# ac-adapter.net
KiCad netlist of a schematic drawn in EAGLE
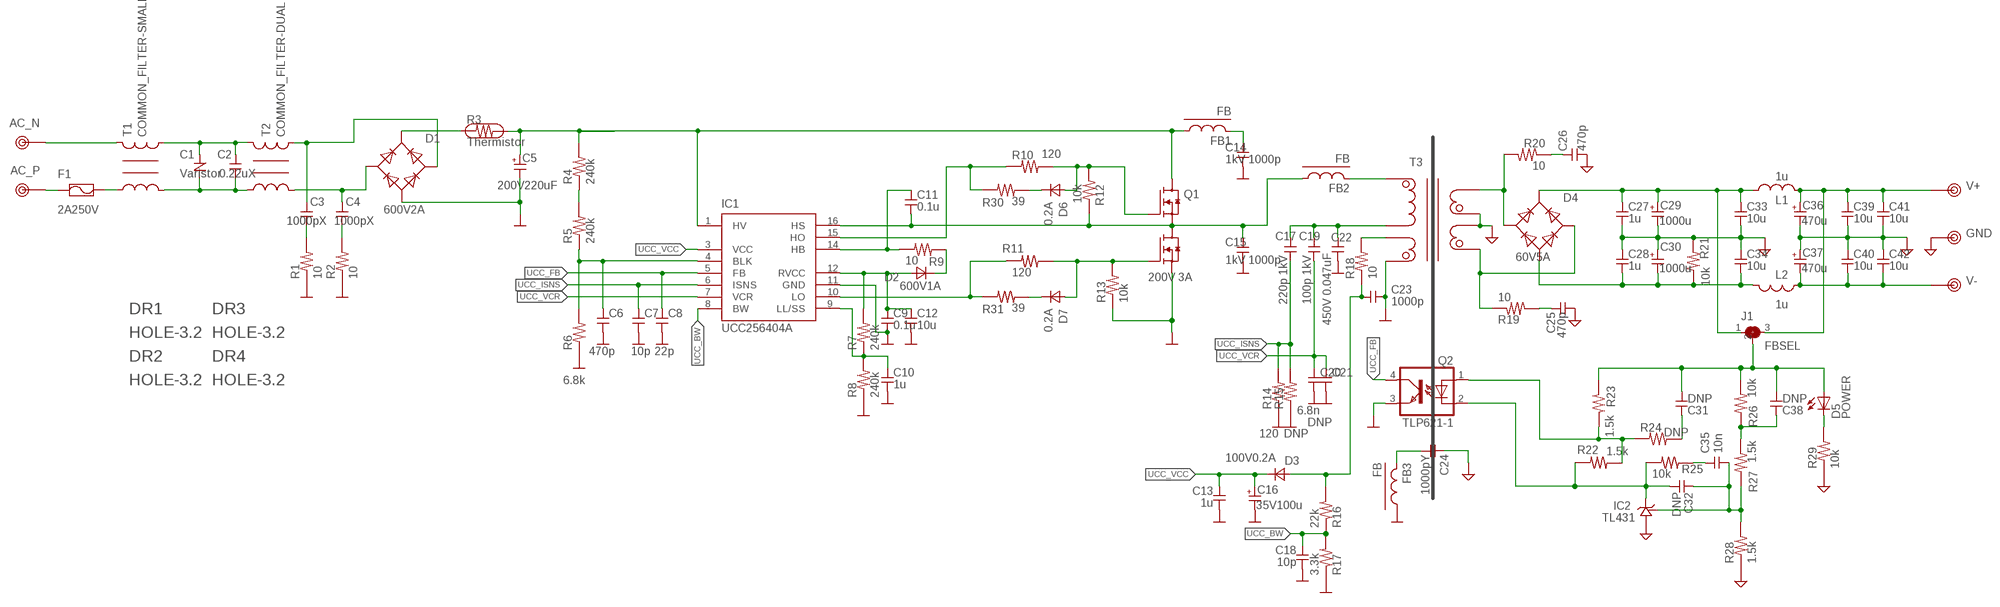
[diagram p0: schematic, sheet 1]

(export (version "E")
  (design (tool "Eeschema 10.0.6"))
  (components
    (comp (ref "C1")
      (value "Varistor")
      (footprint "eagle-import:V050")
      (libsource (lib "eagle-import") (part "VARISTOR"))
    )
    (comp (ref "C2")
      (value "0.22uX")
      (footprint "eagle-import:X-CAPACITER")
      (libsource (lib "eagle-import") (part "C-X"))
    )
    (comp (ref "C3")
      (value "1000pX")
      (footprint "eagle-import:3216")
      (libsource (lib "eagle-import") (part "C-3216"))
    )
    (comp (ref "C4")
      (value "1000pX")
      (footprint "eagle-import:3216")
      (libsource (lib "eagle-import") (part "C-3216"))
    )
    (comp (ref "C5")
      (value "200V220uF")
      (footprint "eagle-import:E5-16A3")
      (libsource (lib "eagle-import") (part "CPOLE7.5-16A3"))
    )
    (comp (ref "C6")
      (value "470p")
      (footprint "eagle-import:1608")
      (libsource (lib "eagle-import") (part "C-1608"))
    )
    (comp (ref "C7")
      (value "10p")
      (footprint "eagle-import:1608")
      (libsource (lib "eagle-import") (part "C-1608"))
    )
    (comp (ref "C8")
      (value "22p")
      (footprint "eagle-import:1608")
      (libsource (lib "eagle-import") (part "C-1608"))
    )
    (comp (ref "C9")
      (value "0.1u")
      (footprint "eagle-import:1608")
      (libsource (lib "eagle-import") (part "C-1608"))
    )
    (comp (ref "C10")
      (value "1u")
      (footprint "eagle-import:1608")
      (libsource (lib "eagle-import") (part "C-1608"))
    )
    (comp (ref "C11")
      (value "0.1u")
      (footprint "eagle-import:1608")
      (libsource (lib "eagle-import") (part "C-1608"))
    )
    (comp (ref "C12")
      (value "10u")
      (footprint "eagle-import:2012")
      (libsource (lib "eagle-import") (part "C-2012"))
    )
    (comp (ref "C13")
      (value "1u")
      (footprint "eagle-import:1608")
      (libsource (lib "eagle-import") (part "C-1608"))
    )
    (comp (ref "C14")
      (value "1kV 1000p")
      (footprint "eagle-import:3225")
      (libsource (lib "eagle-import") (part "C-3225"))
    )
    (comp (ref "C15")
      (value "1kV 1000p")
      (footprint "eagle-import:3225")
      (libsource (lib "eagle-import") (part "C-3225"))
    )
    (comp (ref "C16")
      (value "35V100u")
      (footprint "eagle-import:E2,5-8")
      (libsource (lib "eagle-import") (part "CPOLE2.5-8"))
    )
    (comp (ref "C17")
      (value "220p 1kV")
      (footprint "eagle-import:3225")
      (libsource (lib "eagle-import") (part "C-3225"))
    )
    (comp (ref "C18")
      (value "10p")
      (footprint "eagle-import:1608")
      (libsource (lib "eagle-import") (part "C-1608"))
    )
    (comp (ref "C19")
      (value "100p 1kV")
      (footprint "eagle-import:3225")
      (libsource (lib "eagle-import") (part "C-3225"))
    )
    (comp (ref "C20")
      (value "6.8n")
      (footprint "eagle-import:1608")
      (libsource (lib "eagle-import") (part "C-1608"))
    )
    (comp (ref "C21")
      (value "DNP")
      (footprint "eagle-import:1608")
      (libsource (lib "eagle-import") (part "C-1608"))
    )
    (comp (ref "C22")
      (value "450V 0.047uF")
      (footprint "eagle-import:C125")
      (libsource (lib "eagle-import") (part "C-12.5"))
    )
    (comp (ref "C23")
      (value "1000p")
      (footprint "eagle-import:1608")
      (libsource (lib "eagle-import") (part "C-1608"))
    )
    (comp (ref "C24")
      (value "1000pY")
      (footprint "eagle-import:Y-CAPACITER")
      (libsource (lib "eagle-import") (part "C-Y"))
    )
    (comp (ref "C25")
      (value "470p")
      (footprint "eagle-import:1608")
      (libsource (lib "eagle-import") (part "C-1608"))
    )
    (comp (ref "C26")
      (value "470p")
      (footprint "eagle-import:1608")
      (libsource (lib "eagle-import") (part "C-1608"))
    )
    (comp (ref "C27")
      (value "1u")
      (footprint "eagle-import:2012-2")
      (libsource (lib "eagle-import") (part "C-2012-2"))
    )
    (comp (ref "C28")
      (value "1u")
      (footprint "eagle-import:2012-2")
      (libsource (lib "eagle-import") (part "C-2012-2"))
    )
    (comp (ref "C29")
      (value "1000u")
      (footprint "eagle-import:E5-13")
      (libsource (lib "eagle-import") (part "CPOLE5-13"))
    )
    (comp (ref "C30")
      (value "1000u")
      (footprint "eagle-import:E5-13")
      (libsource (lib "eagle-import") (part "CPOLE5-13"))
    )
    (comp (ref "C31")
      (value "DNP")
      (footprint "eagle-import:1608")
      (libsource (lib "eagle-import") (part "C-1608"))
    )
    (comp (ref "C32")
      (value "DNP")
      (footprint "eagle-import:1608")
      (libsource (lib "eagle-import") (part "C-1608"))
    )
    (comp (ref "C33")
      (value "10u")
      (footprint "eagle-import:3225-3")
      (libsource (lib "eagle-import") (part "C-3225-3"))
    )
    (comp (ref "C34")
      (value "10u")
      (footprint "eagle-import:3225-3")
      (libsource (lib "eagle-import") (part "C-3225-3"))
    )
    (comp (ref "C35")
      (value "10n")
      (footprint "eagle-import:1608")
      (libsource (lib "eagle-import") (part "C-1608"))
    )
    (comp (ref "C36")
      (value "470u")
      (footprint "eagle-import:E5-10")
      (libsource (lib "eagle-import") (part "CPOLE5-10"))
    )
    (comp (ref "C37")
      (value "470u")
      (footprint "eagle-import:E5-10")
      (libsource (lib "eagle-import") (part "CPOLE5-10"))
    )
    (comp (ref "C38")
      (value "DNP")
      (footprint "eagle-import:1608")
      (libsource (lib "eagle-import") (part "C-1608"))
    )
    (comp (ref "C39")
      (value "10u")
      (footprint "eagle-import:3225-3")
      (libsource (lib "eagle-import") (part "C-3225-3"))
    )
    (comp (ref "C40")
      (value "10u")
      (footprint "eagle-import:3225-3")
      (libsource (lib "eagle-import") (part "C-3225-3"))
    )
    (comp (ref "C41")
      (value "10u")
      (footprint "eagle-import:4532-2")
      (libsource (lib "eagle-import") (part "C-4532-2"))
    )
    (comp (ref "C42")
      (value "10u")
      (footprint "eagle-import:4532-2")
      (libsource (lib "eagle-import") (part "C-4532-2"))
    )
    (comp (ref "D1")
      (value "600V2A")
      (footprint "eagle-import:GBU8A")
      (libsource (lib "eagle-import") (part "DIODE4-GBU8A"))
    )
    (comp (ref "D2")
      (value "600V1A")
      (footprint "eagle-import:SOD123")
      (libsource (lib "eagle-import") (part "DIODE-1N4148W"))
    )
    (comp (ref "D3")
      (value "100V0.2A")
      (footprint "eagle-import:SOD123")
      (libsource (lib "eagle-import") (part "DIODE-1N4148W"))
    )
    (comp (ref "D4")
      (value "60V5A")
      (footprint "eagle-import:RBA-406")
      (libsource (lib "eagle-import") (part "DIODE4-RBA406B"))
    )
    (comp (ref "D5")
      (value "POWER")
      (footprint "eagle-import:D1608")
      (libsource (lib "eagle-import") (part "LED-SMD1608"))
    )
    (comp (ref "D6")
      (value "0.2A")
      (footprint "eagle-import:SOD123")
      (libsource (lib "eagle-import") (part "DIODE-1N4148W"))
    )
    (comp (ref "D7")
      (value "0.2A")
      (footprint "eagle-import:SOD123")
      (libsource (lib "eagle-import") (part "DIODE-1N4148W"))
    )
    (comp (ref "DR1")
      (value "HOLE-3.2")
      (footprint "eagle-import:HOLE_3.2")
      (libsource (lib "eagle-import") (part "HOLE-3.2"))
    )
    (comp (ref "DR2")
      (value "HOLE-3.2")
      (footprint "eagle-import:HOLE_3.2")
      (libsource (lib "eagle-import") (part "HOLE-3.2"))
    )
    (comp (ref "DR3")
      (value "HOLE-3.2")
      (footprint "eagle-import:HOLE_3.2")
      (libsource (lib "eagle-import") (part "HOLE-3.2"))
    )
    (comp (ref "DR4")
      (value "HOLE-3.2")
      (footprint "eagle-import:HOLE_3.2")
      (libsource (lib "eagle-import") (part "HOLE-3.2"))
    )
    (comp (ref "F1")
      (value "2A250V")
      (footprint "eagle-import:FUSE-5")
      (libsource (lib "eagle-import") (part "FUSE-5"))
    )
    (comp (ref "FB1")
      (value "FB")
      (footprint "eagle-import:2012-FB")
      (libsource (lib "eagle-import") (part "FB2012-FB"))
    )
    (comp (ref "FB2")
      (value "FB")
      (footprint "eagle-import:3216-J")
      (libsource (lib "eagle-import") (part "FB-3216"))
    )
    (comp (ref "FB3")
      (value "FB")
      (footprint "eagle-import:2012-FB")
      (libsource (lib "eagle-import") (part "FB2012-FB"))
    )
    (comp (ref "IC1")
      (value "UCC256404A")
      (footprint "eagle-import:SO16-LACK3-13")
      (libsource (lib "eagle-import") (part "UCC25640X"))
    )
    (comp (ref "IC2")
      (value "TL431")
      (footprint "eagle-import:TO-92")
      (libsource (lib "eagle-import") (part "TL431"))
    )
    (comp (ref "J1")
      (value "FBSEL")
      (footprint "eagle-import:2012-3-J")
      (libsource (lib "eagle-import") (part "SJ-3-2012"))
    )
    (comp (ref "L1")
      (value "1u")
      (footprint "eagle-import:L5-7,5")
      (libsource (lib "eagle-import") (part "L-5"))
    )
    (comp (ref "L2")
      (value "1u")
      (footprint "eagle-import:L5-7,5")
      (libsource (lib "eagle-import") (part "L-5"))
    )
    (comp (ref "Q1")
      (value "200V 3A")
      (footprint "eagle-import:NMOS-FET_HALF")
      (libsource (lib "eagle-import") (part "NMOS_FET_HALF"))
    )
    (comp (ref "Q2")
      (value "TLP621-1")
      (footprint "eagle-import:DIL04")
      (libsource (lib "eagle-import") (part "TLP621-1"))
    )
    (comp (ref "R1")
      (value "10")
      (footprint "eagle-import:2012")
      (libsource (lib "eagle-import") (part "R-2012"))
    )
    (comp (ref "R2")
      (value "10")
      (footprint "eagle-import:2012")
      (libsource (lib "eagle-import") (part "R-2012"))
    )
    (comp (ref "R3")
      (value "Thermistor")
      (footprint "eagle-import:THERMISTOR090")
      (libsource (lib "eagle-import") (part "THERMISTOR"))
    )
    (comp (ref "R4")
      (value "240k")
      (footprint "eagle-import:1608")
      (libsource (lib "eagle-import") (part "R-1608"))
    )
    (comp (ref "R5")
      (value "240k")
      (footprint "eagle-import:1608")
      (libsource (lib "eagle-import") (part "R-1608"))
    )
    (comp (ref "R6")
      (value "6.8k")
      (footprint "eagle-import:1608")
      (libsource (lib "eagle-import") (part "R-1608"))
    )
    (comp (ref "R7")
      (value "240k")
      (footprint "eagle-import:1608")
      (libsource (lib "eagle-import") (part "R-1608"))
    )
    (comp (ref "R8")
      (value "240k")
      (footprint "eagle-import:1608")
      (libsource (lib "eagle-import") (part "R-1608"))
    )
    (comp (ref "R9")
      (value "10")
      (footprint "eagle-import:1608")
      (libsource (lib "eagle-import") (part "R-1608"))
    )
    (comp (ref "R10")
      (value "120")
      (footprint "eagle-import:1608")
      (libsource (lib "eagle-import") (part "R-1608"))
    )
    (comp (ref "R11")
      (value "120")
      (footprint "eagle-import:1608")
      (libsource (lib "eagle-import") (part "R-1608"))
    )
    (comp (ref "R12")
      (value "10k")
      (footprint "eagle-import:1608")
      (libsource (lib "eagle-import") (part "R-1608"))
    )
    (comp (ref "R13")
      (value "10k")
      (footprint "eagle-import:1608")
      (libsource (lib "eagle-import") (part "R-1608"))
    )
    (comp (ref "R14")
      (value "120")
      (footprint "eagle-import:1608")
      (libsource (lib "eagle-import") (part "R-1608"))
    )
    (comp (ref "R15")
      (value "DNP")
      (footprint "eagle-import:1608")
      (libsource (lib "eagle-import") (part "R-1608"))
    )
    (comp (ref "R16")
      (value "22k")
      (footprint "eagle-import:1608")
      (libsource (lib "eagle-import") (part "R-1608"))
    )
    (comp (ref "R17")
      (value "3.3k")
      (footprint "eagle-import:1608")
      (libsource (lib "eagle-import") (part "R-1608"))
    )
    (comp (ref "R18")
      (value "10")
      (footprint "eagle-import:2012")
      (libsource (lib "eagle-import") (part "R-2012"))
    )
    (comp (ref "R19")
      (value "10")
      (footprint "eagle-import:2012")
      (libsource (lib "eagle-import") (part "R-2012"))
    )
    (comp (ref "R20")
      (value "10")
      (footprint "eagle-import:2012")
      (libsource (lib "eagle-import") (part "R-2012"))
    )
    (comp (ref "R21")
      (value "10k")
      (footprint "eagle-import:1608")
      (libsource (lib "eagle-import") (part "R-1608"))
    )
    (comp (ref "R22")
      (value "1.5k")
      (footprint "eagle-import:1608")
      (libsource (lib "eagle-import") (part "R-1608"))
    )
    (comp (ref "R23")
      (value "1.5k")
      (footprint "eagle-import:1608")
      (libsource (lib "eagle-import") (part "R-1608"))
    )
    (comp (ref "R24")
      (value "DNP")
      (footprint "eagle-import:1608")
      (libsource (lib "eagle-import") (part "R-1608"))
    )
    (comp (ref "R25")
      (value "10k")
      (footprint "eagle-import:1608")
      (libsource (lib "eagle-import") (part "R-1608"))
    )
    (comp (ref "R26")
      (value "10k")
      (footprint "eagle-import:1608")
      (libsource (lib "eagle-import") (part "R-1608"))
    )
    (comp (ref "R27")
      (value "1.5k")
      (footprint "eagle-import:1608")
      (libsource (lib "eagle-import") (part "R-1608"))
    )
    (comp (ref "R28")
      (value "1.5k")
      (footprint "eagle-import:1608")
      (libsource (lib "eagle-import") (part "R-1608"))
    )
    (comp (ref "R29")
      (value "10k")
      (footprint "eagle-import:1608")
      (libsource (lib "eagle-import") (part "R-1608"))
    )
    (comp (ref "R30")
      (value "39")
      (footprint "eagle-import:1608")
      (libsource (lib "eagle-import") (part "R-1608"))
    )
    (comp (ref "R31")
      (value "39")
      (footprint "eagle-import:1608")
      (libsource (lib "eagle-import") (part "R-1608"))
    )
    (comp (ref "T1")
      (value "COMMON_FILTER-SMALL")
      (footprint "eagle-import:COMMON_FILTER__SMALL")
      (libsource (lib "eagle-import") (part "COMMON_FILTER-SMALL"))
    )
    (comp (ref "T2")
      (value "COMMON_FILTER-DUAL")
      (footprint "eagle-import:SU10VFC-DUAL")
      (libsource (lib "eagle-import") (part "COMMON_FILTER-DUAL"))
    )
    (comp (ref "T3")
      (value "TRANSFORMAER_FLYBACK-ETD34")
      (footprint "eagle-import:BETD34LLC")
      (libsource (lib "eagle-import") (part "TRANSFORMAER_FLYBACK-ETD34"))
    )
    (comp (ref "TP1")
      (value "AC_N")
      (footprint "eagle-import:TESTPIN-LARGE")
      (libsource (lib "eagle-import") (part "TESTPIN-LARGE"))
    )
    (comp (ref "TP2")
      (value "AC_P")
      (footprint "eagle-import:TESTPIN-LARGE")
      (libsource (lib "eagle-import") (part "TESTPIN-LARGE"))
    )
    (comp (ref "TP3")
      (value "V+")
      (footprint "eagle-import:TESTPIN-LARGE")
      (libsource (lib "eagle-import") (part "TESTPIN-LARGE"))
    )
    (comp (ref "TP4")
      (value "V-")
      (footprint "eagle-import:TESTPIN-LARGE")
      (libsource (lib "eagle-import") (part "TESTPIN-LARGE"))
    )
    (comp (ref "TP5")
      (value "GND")
      (footprint "eagle-import:TESTPIN-LARGE")
      (libsource (lib "eagle-import") (part "TESTPIN-LARGE"))
    )
  )
  (nets
    (net (code "1") (name "GND") (class "Default")
      (node (ref "C24") (pin "1") (pinfunction "1_1") (pintype "passive"))
      (node (ref "C25") (pin "2") (pinfunction "2_2") (pintype "passive"))
      (node (ref "C26") (pin "2") (pinfunction "2_2") (pintype "passive"))
      (node (ref "C27") (pin "2") (pinfunction "2_2") (pintype "passive"))
      (node (ref "C28") (pin "1") (pinfunction "1_1") (pintype "passive"))
      (node (ref "C29") (pin "-") (pinfunction "2_-") (pintype "passive"))
      (node (ref "C30") (pin "+") (pinfunction "1_+") (pintype "passive"))
      (node (ref "C33") (pin "2") (pinfunction "2_2") (pintype "passive"))
      (node (ref "C34") (pin "1") (pinfunction "1_1") (pintype "passive"))
      (node (ref "C36") (pin "-") (pinfunction "2_-") (pintype "passive"))
      (node (ref "C37") (pin "+") (pinfunction "1_+") (pintype "passive"))
      (node (ref "C39") (pin "2") (pinfunction "2_2") (pintype "passive"))
      (node (ref "C40") (pin "1") (pinfunction "1_1") (pintype "passive"))
      (node (ref "C41") (pin "2") (pinfunction "2_2") (pintype "passive"))
      (node (ref "C42") (pin "1") (pinfunction "1_1") (pintype "passive"))
      (node (ref "IC2") (pin "2") (pinfunction "GND_2") (pintype "bidirectional"))
      (node (ref "R21") (pin "1") (pinfunction "1_1") (pintype "passive"))
      (node (ref "R28") (pin "1") (pinfunction "1_1") (pintype "passive"))
      (node (ref "R29") (pin "1") (pinfunction "1_1") (pintype "passive"))
      (node (ref "T3") (pin "11") (pinfunction "L4_N_11") (pintype "passive"))
      (node (ref "T3") (pin "8") (pinfunction "L3_P_8") (pintype "passive"))
      (node (ref "TP5") (pin "1") (pinfunction "1_1") (pintype "passive"))
    )
    (net (code "2") (name "Net-(C1-Pad1)") (class "Default")
      (node (ref "C1") (pin "1") (pinfunction "1_1") (pintype "passive"))
      (node (ref "C2") (pin "1") (pinfunction "1_1") (pintype "passive"))
      (node (ref "T1") (pin "3") (pinfunction "3_3") (pintype "passive"))
      (node (ref "T2") (pin "1") (pinfunction "1_1") (pintype "passive"))
      (node (ref "T2") (pin "5") (pinfunction "1_5") (pintype "passive"))
    )
    (net (code "3") (name "Net-(C1-Pad2)") (class "Default")
      (node (ref "C1") (pin "2") (pinfunction "2_2") (pintype "passive"))
      (node (ref "C2") (pin "2") (pinfunction "2_2") (pintype "passive"))
      (node (ref "T1") (pin "2") (pinfunction "2_2") (pintype "passive"))
      (node (ref "T2") (pin "4") (pinfunction "4_4") (pintype "passive"))
    )
    (net (code "4") (name "Net-(C3-Pad2)") (class "Default")
      (node (ref "C3") (pin "2") (pinfunction "2_2") (pintype "passive"))
      (node (ref "R1") (pin "2") (pinfunction "2_2") (pintype "passive"))
    )
    (net (code "5") (name "Net-(C4-Pad2)") (class "Default")
      (node (ref "C4") (pin "2") (pinfunction "2_2") (pintype "passive"))
      (node (ref "R2") (pin "2") (pinfunction "2_2") (pintype "passive"))
    )
    (net (code "6") (name "Net-(C5-1)") (class "Default")
      (node (ref "C5") (pin "+") (pinfunction "1_+") (pintype "passive"))
      (node (ref "FB1") (pin "1") (pinfunction "1_1") (pintype "passive"))
      (node (ref "IC1") (pin "1") (pinfunction "HV_1") (pintype "input"))
      (node (ref "Q1") (pin "V+") (pinfunction "V+_V+") (pintype "passive"))
      (node (ref "R3") (pin "2") (pinfunction "2_2") (pintype "passive"))
      (node (ref "R4") (pin "2") (pinfunction "2_2") (pintype "passive"))
    )
    (net (code "7") (name "Net-(C14-Pad1)") (class "Default")
      (node (ref "C14") (pin "1") (pinfunction "1_1") (pintype "passive"))
      (node (ref "FB1") (pin "2") (pinfunction "2_2") (pintype "passive"))
    )
    (net (code "8") (name "Net-(C24-Pad2)") (class "Default")
      (node (ref "C24") (pin "2") (pinfunction "2_2") (pintype "passive"))
      (node (ref "FB3") (pin "2") (pinfunction "2_2") (pintype "passive"))
    )
    (net (code "9") (name "Net-(C25-Pad1)") (class "Default")
      (node (ref "C25") (pin "1") (pinfunction "1_1") (pintype "passive"))
      (node (ref "R19") (pin "2") (pinfunction "2_2") (pintype "passive"))
    )
    (net (code "10") (name "Net-(C26-Pad1)") (class "Default")
      (node (ref "C26") (pin "1") (pinfunction "1_1") (pintype "passive"))
      (node (ref "R20") (pin "1") (pinfunction "1_1") (pintype "passive"))
    )
    (net (code "11") (name "Net-(C29-1)") (class "Default")
      (node (ref "C27") (pin "1") (pinfunction "1_1") (pintype "passive"))
      (node (ref "C29") (pin "+") (pinfunction "1_+") (pintype "passive"))
      (node (ref "C33") (pin "1") (pinfunction "1_1") (pintype "passive"))
      (node (ref "D4") (pin "1") (pinfunction "V+_1") (pintype "passive"))
      (node (ref "J1") (pin "1") (pinfunction "1_1") (pintype "passive"))
      (node (ref "L1") (pin "2") (pinfunction "1_2") (pintype "passive"))
    )
    (net (code "12") (name "Net-(C30-2)") (class "Default")
      (node (ref "C28") (pin "2") (pinfunction "2_2") (pintype "passive"))
      (node (ref "C30") (pin "-") (pinfunction "2_-") (pintype "passive"))
      (node (ref "C34") (pin "2") (pinfunction "2_2") (pintype "passive"))
      (node (ref "D4") (pin "4") (pinfunction "V-_4") (pintype "passive"))
      (node (ref "L2") (pin "2") (pinfunction "1_2") (pintype "passive"))
      (node (ref "R21") (pin "2") (pinfunction "2_2") (pintype "passive"))
    )
    (net (code "13") (name "Net-(C31-Pad1)") (class "Default")
      (node (ref "C31") (pin "1") (pinfunction "1_1") (pintype "passive"))
      (node (ref "R24") (pin "2") (pinfunction "2_2") (pintype "passive"))
    )
    (net (code "14") (name "Net-(C31-Pad2)") (class "Default")
      (node (ref "C31") (pin "2") (pinfunction "2_2") (pintype "passive"))
      (node (ref "C38") (pin "2") (pinfunction "2_2") (pintype "passive"))
      (node (ref "D5") (pin "A") (pinfunction "A_A") (pintype "passive"))
      (node (ref "J1") (pin "2") (pinfunction "2_2") (pintype "passive"))
      (node (ref "R23") (pin "1") (pinfunction "1_1") (pintype "passive"))
      (node (ref "R26") (pin "2") (pinfunction "2_2") (pintype "passive"))
    )
    (net (code "15") (name "Net-(C35-Pad1)") (class "Default")
      (node (ref "C35") (pin "1") (pinfunction "1_1") (pintype "passive"))
      (node (ref "R25") (pin "2") (pinfunction "2_2") (pintype "passive"))
    )
    (net (code "16") (name "Net-(C36-1)") (class "Default")
      (node (ref "C36") (pin "+") (pinfunction "1_+") (pintype "passive"))
      (node (ref "C39") (pin "1") (pinfunction "1_1") (pintype "passive"))
      (node (ref "C41") (pin "1") (pinfunction "1_1") (pintype "passive"))
      (node (ref "J1") (pin "3") (pinfunction "3_3") (pintype "passive"))
      (node (ref "L1") (pin "1") (pinfunction "2_1") (pintype "passive"))
      (node (ref "TP3") (pin "1") (pinfunction "1_1") (pintype "passive"))
    )
    (net (code "17") (name "Net-(C37-2)") (class "Default")
      (node (ref "C37") (pin "-") (pinfunction "2_-") (pintype "passive"))
      (node (ref "C40") (pin "2") (pinfunction "2_2") (pintype "passive"))
      (node (ref "C42") (pin "2") (pinfunction "2_2") (pintype "passive"))
      (node (ref "L2") (pin "1") (pinfunction "2_1") (pintype "passive"))
      (node (ref "TP4") (pin "1") (pinfunction "1_1") (pintype "passive"))
    )
    (net (code "18") (name "Net-(C38-Pad1)") (class "Default")
      (node (ref "C38") (pin "1") (pinfunction "1_1") (pintype "passive"))
      (node (ref "R26") (pin "1") (pinfunction "1_1") (pintype "passive"))
      (node (ref "R27") (pin "2") (pinfunction "2_2") (pintype "passive"))
    )
    (net (code "19") (name "Net-(D1-AC1)") (class "Default")
      (node (ref "C4") (pin "1") (pinfunction "1_1") (pintype "passive"))
      (node (ref "D1") (pin "2") (pinfunction "AC1_2") (pintype "passive"))
      (node (ref "T2") (pin "3") (pinfunction "3_3") (pintype "passive"))
    )
    (net (code "20") (name "Net-(D1-AC2)") (class "Default")
      (node (ref "C3") (pin "1") (pinfunction "1_1") (pintype "passive"))
      (node (ref "D1") (pin "3") (pinfunction "AC2_3") (pintype "passive"))
      (node (ref "T2") (pin "2") (pinfunction "2_2") (pintype "passive"))
      (node (ref "T2") (pin "6") (pinfunction "2_6") (pintype "passive"))
    )
    (net (code "21") (name "Net-(D1-V+)") (class "Default")
      (node (ref "D1") (pin "1") (pinfunction "V+_1") (pintype "passive"))
      (node (ref "R3") (pin "1") (pinfunction "1_1") (pintype "passive"))
    )
    (net (code "22") (name "Net-(D2-A)") (class "Default")
      (node (ref "C12") (pin "1") (pinfunction "1_1") (pintype "passive"))
      (node (ref "C9") (pin "1") (pinfunction "1_1") (pintype "passive"))
      (node (ref "D2") (pin "1") (pinfunction "A_1") (pintype "passive"))
      (node (ref "IC1") (pin "12") (pinfunction "RVCC_12") (pintype "input"))
      (node (ref "R7") (pin "2") (pinfunction "2_2") (pintype "passive"))
    )
    (net (code "23") (name "Net-(D2-K)") (class "Default")
      (node (ref "D2") (pin "2") (pinfunction "K_2") (pintype "passive"))
      (node (ref "R9") (pin "2") (pinfunction "2_2") (pintype "passive"))
    )
    (net (code "24") (name "Net-(D3-A)") (class "Default")
      (node (ref "C23") (pin "1") (pinfunction "1_1") (pintype "passive"))
      (node (ref "D3") (pin "1") (pinfunction "A_1") (pintype "passive"))
      (node (ref "R16") (pin "2") (pinfunction "2_2") (pintype "passive"))
      (node (ref "R18") (pin "1") (pinfunction "1_1") (pintype "passive"))
    )
    (net (code "25") (name "Net-(D4-AC1)") (class "Default")
      (node (ref "D4") (pin "2") (pinfunction "AC1_2") (pintype "passive"))
      (node (ref "R20") (pin "2") (pinfunction "2_2") (pintype "passive"))
      (node (ref "T3") (pin "9") (pinfunction "L3_N_9") (pintype "passive"))
    )
    (net (code "26") (name "Net-(D4-AC2)") (class "Default")
      (node (ref "D4") (pin "3") (pinfunction "AC2_3") (pintype "passive"))
      (node (ref "R19") (pin "1") (pinfunction "1_1") (pintype "passive"))
      (node (ref "T3") (pin "10") (pinfunction "L4_P_10") (pintype "passive"))
    )
    (net (code "27") (name "Net-(D5-PadK)") (class "Default")
      (node (ref "D5") (pin "K") (pinfunction "K_K") (pintype "passive"))
      (node (ref "R29") (pin "2") (pinfunction "2_2") (pintype "passive"))
    )
    (net (code "28") (name "Net-(D6-A)") (class "Default")
      (node (ref "D6") (pin "1") (pinfunction "A_1") (pintype "passive"))
      (node (ref "Q1") (pin "GT") (pinfunction "GT_GT") (pintype "passive"))
      (node (ref "R10") (pin "2") (pinfunction "2_2") (pintype "passive"))
      (node (ref "R12") (pin "1") (pinfunction "1_1") (pintype "passive"))
    )
    (net (code "29") (name "Net-(D6-K)") (class "Default")
      (node (ref "D6") (pin "2") (pinfunction "K_2") (pintype "passive"))
      (node (ref "R30") (pin "2") (pinfunction "2_2") (pintype "passive"))
    )
    (net (code "30") (name "Net-(D7-A)") (class "Default")
      (node (ref "D7") (pin "1") (pinfunction "A_1") (pintype "passive"))
      (node (ref "Q1") (pin "GB") (pinfunction "GB_GB") (pintype "passive"))
      (node (ref "R11") (pin "1") (pinfunction "1_1") (pintype "passive"))
      (node (ref "R13") (pin "2") (pinfunction "2_2") (pintype "passive"))
    )
    (net (code "31") (name "Net-(D7-K)") (class "Default")
      (node (ref "D7") (pin "2") (pinfunction "K_2") (pintype "passive"))
      (node (ref "R31") (pin "2") (pinfunction "2_2") (pintype "passive"))
    )
    (net (code "32") (name "Net-(F1-P$1)") (class "Default")
      (node (ref "F1") (pin "1") (pinfunction "P$1_1") (pintype "passive"))
      (node (ref "TP2") (pin "1") (pinfunction "1_1") (pintype "passive"))
    )
    (net (code "33") (name "Net-(F1-P$2)") (class "Default")
      (node (ref "F1") (pin "2") (pinfunction "P$2_2") (pintype "passive"))
      (node (ref "T1") (pin "1") (pinfunction "1_1") (pintype "passive"))
    )
    (net (code "34") (name "Net-(IC1-BLK)") (class "Default")
      (node (ref "C6") (pin "1") (pinfunction "1_1") (pintype "passive"))
      (node (ref "IC1") (pin "4") (pinfunction "BLK_4") (pintype "input"))
      (node (ref "R5") (pin "1") (pinfunction "1_1") (pintype "passive"))
      (node (ref "R6") (pin "2") (pinfunction "2_2") (pintype "passive"))
    )
    (net (code "35") (name "Net-(IC1-HB)") (class "Default")
      (node (ref "C11") (pin "1") (pinfunction "1_1") (pintype "passive"))
      (node (ref "IC1") (pin "14") (pinfunction "HB_14") (pintype "input"))
      (node (ref "R9") (pin "1") (pinfunction "1_1") (pintype "passive"))
    )
    (net (code "36") (name "Net-(IC1-HO)") (class "Default")
      (node (ref "IC1") (pin "15") (pinfunction "HO_15") (pintype "output"))
      (node (ref "R10") (pin "1") (pinfunction "1_1") (pintype "passive"))
      (node (ref "R30") (pin "1") (pinfunction "1_1") (pintype "passive"))
    )
    (net (code "37") (name "Net-(IC1-HS)") (class "Default")
      (node (ref "C11") (pin "2") (pinfunction "2_2") (pintype "passive"))
      (node (ref "C15") (pin "1") (pinfunction "1_1") (pintype "passive"))
      (node (ref "FB2") (pin "1") (pinfunction "1_1") (pintype "passive"))
      (node (ref "IC1") (pin "16") (pinfunction "HS_16") (pintype "input"))
      (node (ref "Q1") (pin "SW") (pinfunction "SW_SW") (pintype "passive"))
      (node (ref "R12") (pin "2") (pinfunction "2_2") (pintype "passive"))
    )
    (net (code "38") (name "Net-(IC1-LL{slash}SS)") (class "Default")
      (node (ref "C10") (pin "1") (pinfunction "1_1") (pintype "passive"))
      (node (ref "IC1") (pin "9") (pinfunction "LL/SS_9") (pintype "input"))
      (node (ref "R7") (pin "1") (pinfunction "1_1") (pintype "passive"))
      (node (ref "R8") (pin "2") (pinfunction "2_2") (pintype "passive"))
    )
    (net (code "39") (name "Net-(IC1-LO)") (class "Default")
      (node (ref "IC1") (pin "10") (pinfunction "LO_10") (pintype "output"))
      (node (ref "R11") (pin "2") (pinfunction "2_2") (pintype "passive"))
      (node (ref "R31") (pin "1") (pinfunction "1_1") (pintype "passive"))
    )
    (net (code "40") (name "Net-(IC2-OUT)") (class "Default")
      (node (ref "C32") (pin "2") (pinfunction "2_2") (pintype "passive"))
      (node (ref "IC2") (pin "3") (pinfunction "OUT_3") (pintype "bidirectional"))
      (node (ref "Q2") (pin "2") (pinfunction "C_2") (pintype "passive"))
      (node (ref "R22") (pin "2") (pinfunction "2_2") (pintype "passive"))
      (node (ref "R25") (pin "1") (pinfunction "1_1") (pintype "passive"))
    )
    (net (code "41") (name "Net-(IC2-REF)") (class "Default")
      (node (ref "C32") (pin "1") (pinfunction "1_1") (pintype "passive"))
      (node (ref "C35") (pin "2") (pinfunction "2_2") (pintype "passive"))
      (node (ref "IC2") (pin "1") (pinfunction "REF_1") (pintype "input"))
      (node (ref "R27") (pin "1") (pinfunction "1_1") (pintype "passive"))
      (node (ref "R28") (pin "2") (pinfunction "2_2") (pintype "passive"))
    )
    (net (code "42") (name "Net-(Q2-A)") (class "Default")
      (node (ref "Q2") (pin "1") (pinfunction "A_1") (pintype "passive"))
      (node (ref "R22") (pin "1") (pinfunction "1_1") (pintype "passive"))
      (node (ref "R23") (pin "2") (pinfunction "2_2") (pintype "passive"))
      (node (ref "R24") (pin "1") (pinfunction "1_1") (pintype "passive"))
    )
    (net (code "43") (name "Net-(R4-Pad1)") (class "Default")
      (node (ref "R4") (pin "1") (pinfunction "1_1") (pintype "passive"))
      (node (ref "R5") (pin "2") (pinfunction "2_2") (pintype "passive"))
    )
    (net (code "44") (name "Net-(T1-Pad4)") (class "Default")
      (node (ref "T1") (pin "4") (pinfunction "4_4") (pintype "passive"))
      (node (ref "TP1") (pin "1") (pinfunction "1_1") (pintype "passive"))
    )
    (net (code "45") (name "Net-(T3-L1_N)") (class "Default")
      (node (ref "C17") (pin "1") (pinfunction "1_1") (pintype "passive"))
      (node (ref "C19") (pin "1") (pinfunction "1_1") (pintype "passive"))
      (node (ref "C22") (pin "1") (pinfunction "1_1") (pintype "passive"))
      (node (ref "T3") (pin "3") (pinfunction "L1_N_3") (pintype "passive"))
    )
    (net (code "46") (name "Net-(T3-L1_P)") (class "Default")
      (node (ref "FB2") (pin "2") (pinfunction "2_2") (pintype "passive"))
      (node (ref "T3") (pin "1") (pinfunction "L1_P_1") (pintype "passive"))
    )
    (net (code "47") (name "Net-(T3-L2_N)") (class "Default")
      (node (ref "R18") (pin "2") (pinfunction "2_2") (pintype "passive"))
      (node (ref "T3") (pin "6") (pinfunction "L2_N_6") (pintype "passive"))
    )
    (net (code "48") (name "PGND") (class "Default")
      (node (ref "C10") (pin "2") (pinfunction "2_2") (pintype "passive"))
      (node (ref "C12") (pin "2") (pinfunction "2_2") (pintype "passive"))
      (node (ref "C13") (pin "2") (pinfunction "2_2") (pintype "passive"))
      (node (ref "C14") (pin "2") (pinfunction "2_2") (pintype "passive"))
      (node (ref "C15") (pin "2") (pinfunction "2_2") (pintype "passive"))
      (node (ref "C16") (pin "-") (pinfunction "2_-") (pintype "passive"))
      (node (ref "C18") (pin "2") (pinfunction "2_2") (pintype "passive"))
      (node (ref "C20") (pin "2") (pinfunction "2_2") (pintype "passive"))
      (node (ref "C21") (pin "2") (pinfunction "2_2") (pintype "passive"))
      (node (ref "C22") (pin "2") (pinfunction "2_2") (pintype "passive"))
      (node (ref "C23") (pin "2") (pinfunction "2_2") (pintype "passive"))
      (node (ref "C5") (pin "-") (pinfunction "2_-") (pintype "passive"))
      (node (ref "C6") (pin "2") (pinfunction "2_2") (pintype "passive"))
      (node (ref "C7") (pin "2") (pinfunction "2_2") (pintype "passive"))
      (node (ref "C8") (pin "2") (pinfunction "2_2") (pintype "passive"))
      (node (ref "C9") (pin "2") (pinfunction "2_2") (pintype "passive"))
      (node (ref "D1") (pin "4") (pinfunction "V-_4") (pintype "passive"))
      (node (ref "FB3") (pin "1") (pinfunction "1_1") (pintype "passive"))
      (node (ref "IC1") (pin "11") (pinfunction "GND_11") (pintype "input"))
      (node (ref "Q1") (pin "V-") (pinfunction "V-_V-") (pintype "passive"))
      (node (ref "Q2") (pin "3") (pinfunction "EMIT_3") (pintype "passive"))
      (node (ref "R1") (pin "1") (pinfunction "1_1") (pintype "passive"))
      (node (ref "R13") (pin "1") (pinfunction "1_1") (pintype "passive"))
      (node (ref "R14") (pin "1") (pinfunction "1_1") (pintype "passive"))
      (node (ref "R15") (pin "1") (pinfunction "1_1") (pintype "passive"))
      (node (ref "R17") (pin "1") (pinfunction "1_1") (pintype "passive"))
      (node (ref "R2") (pin "1") (pinfunction "1_1") (pintype "passive"))
      (node (ref "R6") (pin "1") (pinfunction "1_1") (pintype "passive"))
      (node (ref "R8") (pin "1") (pinfunction "1_1") (pintype "passive"))
      (node (ref "T3") (pin "5") (pinfunction "L2_P_5") (pintype "passive"))
    )
    (net (code "49") (name "UCC_BW") (class "Default")
      (node (ref "C18") (pin "1") (pinfunction "1_1") (pintype "passive"))
      (node (ref "IC1") (pin "8") (pinfunction "BW_8") (pintype "input"))
      (node (ref "R16") (pin "1") (pinfunction "1_1") (pintype "passive"))
      (node (ref "R17") (pin "2") (pinfunction "2_2") (pintype "passive"))
    )
    (net (code "50") (name "UCC_FB") (class "Default")
      (node (ref "C8") (pin "1") (pinfunction "1_1") (pintype "passive"))
      (node (ref "IC1") (pin "5") (pinfunction "FB_5") (pintype "input"))
      (node (ref "Q2") (pin "4") (pinfunction "COL_4") (pintype "passive"))
    )
    (net (code "51") (name "UCC_ISNS") (class "Default")
      (node (ref "C17") (pin "2") (pinfunction "2_2") (pintype "passive"))
      (node (ref "C7") (pin "1") (pinfunction "1_1") (pintype "passive"))
      (node (ref "IC1") (pin "6") (pinfunction "ISNS_6") (pintype "input"))
      (node (ref "R14") (pin "2") (pinfunction "2_2") (pintype "passive"))
      (node (ref "R15") (pin "2") (pinfunction "2_2") (pintype "passive"))
    )
    (net (code "52") (name "UCC_VCC") (class "Default")
      (node (ref "C13") (pin "1") (pinfunction "1_1") (pintype "passive"))
      (node (ref "C16") (pin "+") (pinfunction "1_+") (pintype "passive"))
      (node (ref "D3") (pin "2") (pinfunction "K_2") (pintype "passive"))
      (node (ref "IC1") (pin "3") (pinfunction "VCC_3") (pintype "input"))
    )
    (net (code "53") (name "UCC_VCR") (class "Default")
      (node (ref "C19") (pin "2") (pinfunction "2_2") (pintype "passive"))
      (node (ref "C20") (pin "1") (pinfunction "1_1") (pintype "passive"))
      (node (ref "C21") (pin "1") (pinfunction "1_1") (pintype "passive"))
      (node (ref "IC1") (pin "7") (pinfunction "VCR_7") (pintype "input"))
    )
  )
)
